# SCH_ESP32-S3-DevKitC-1_2026-10-10.net
KiCad netlist of a schematic drawn in EasyEDA
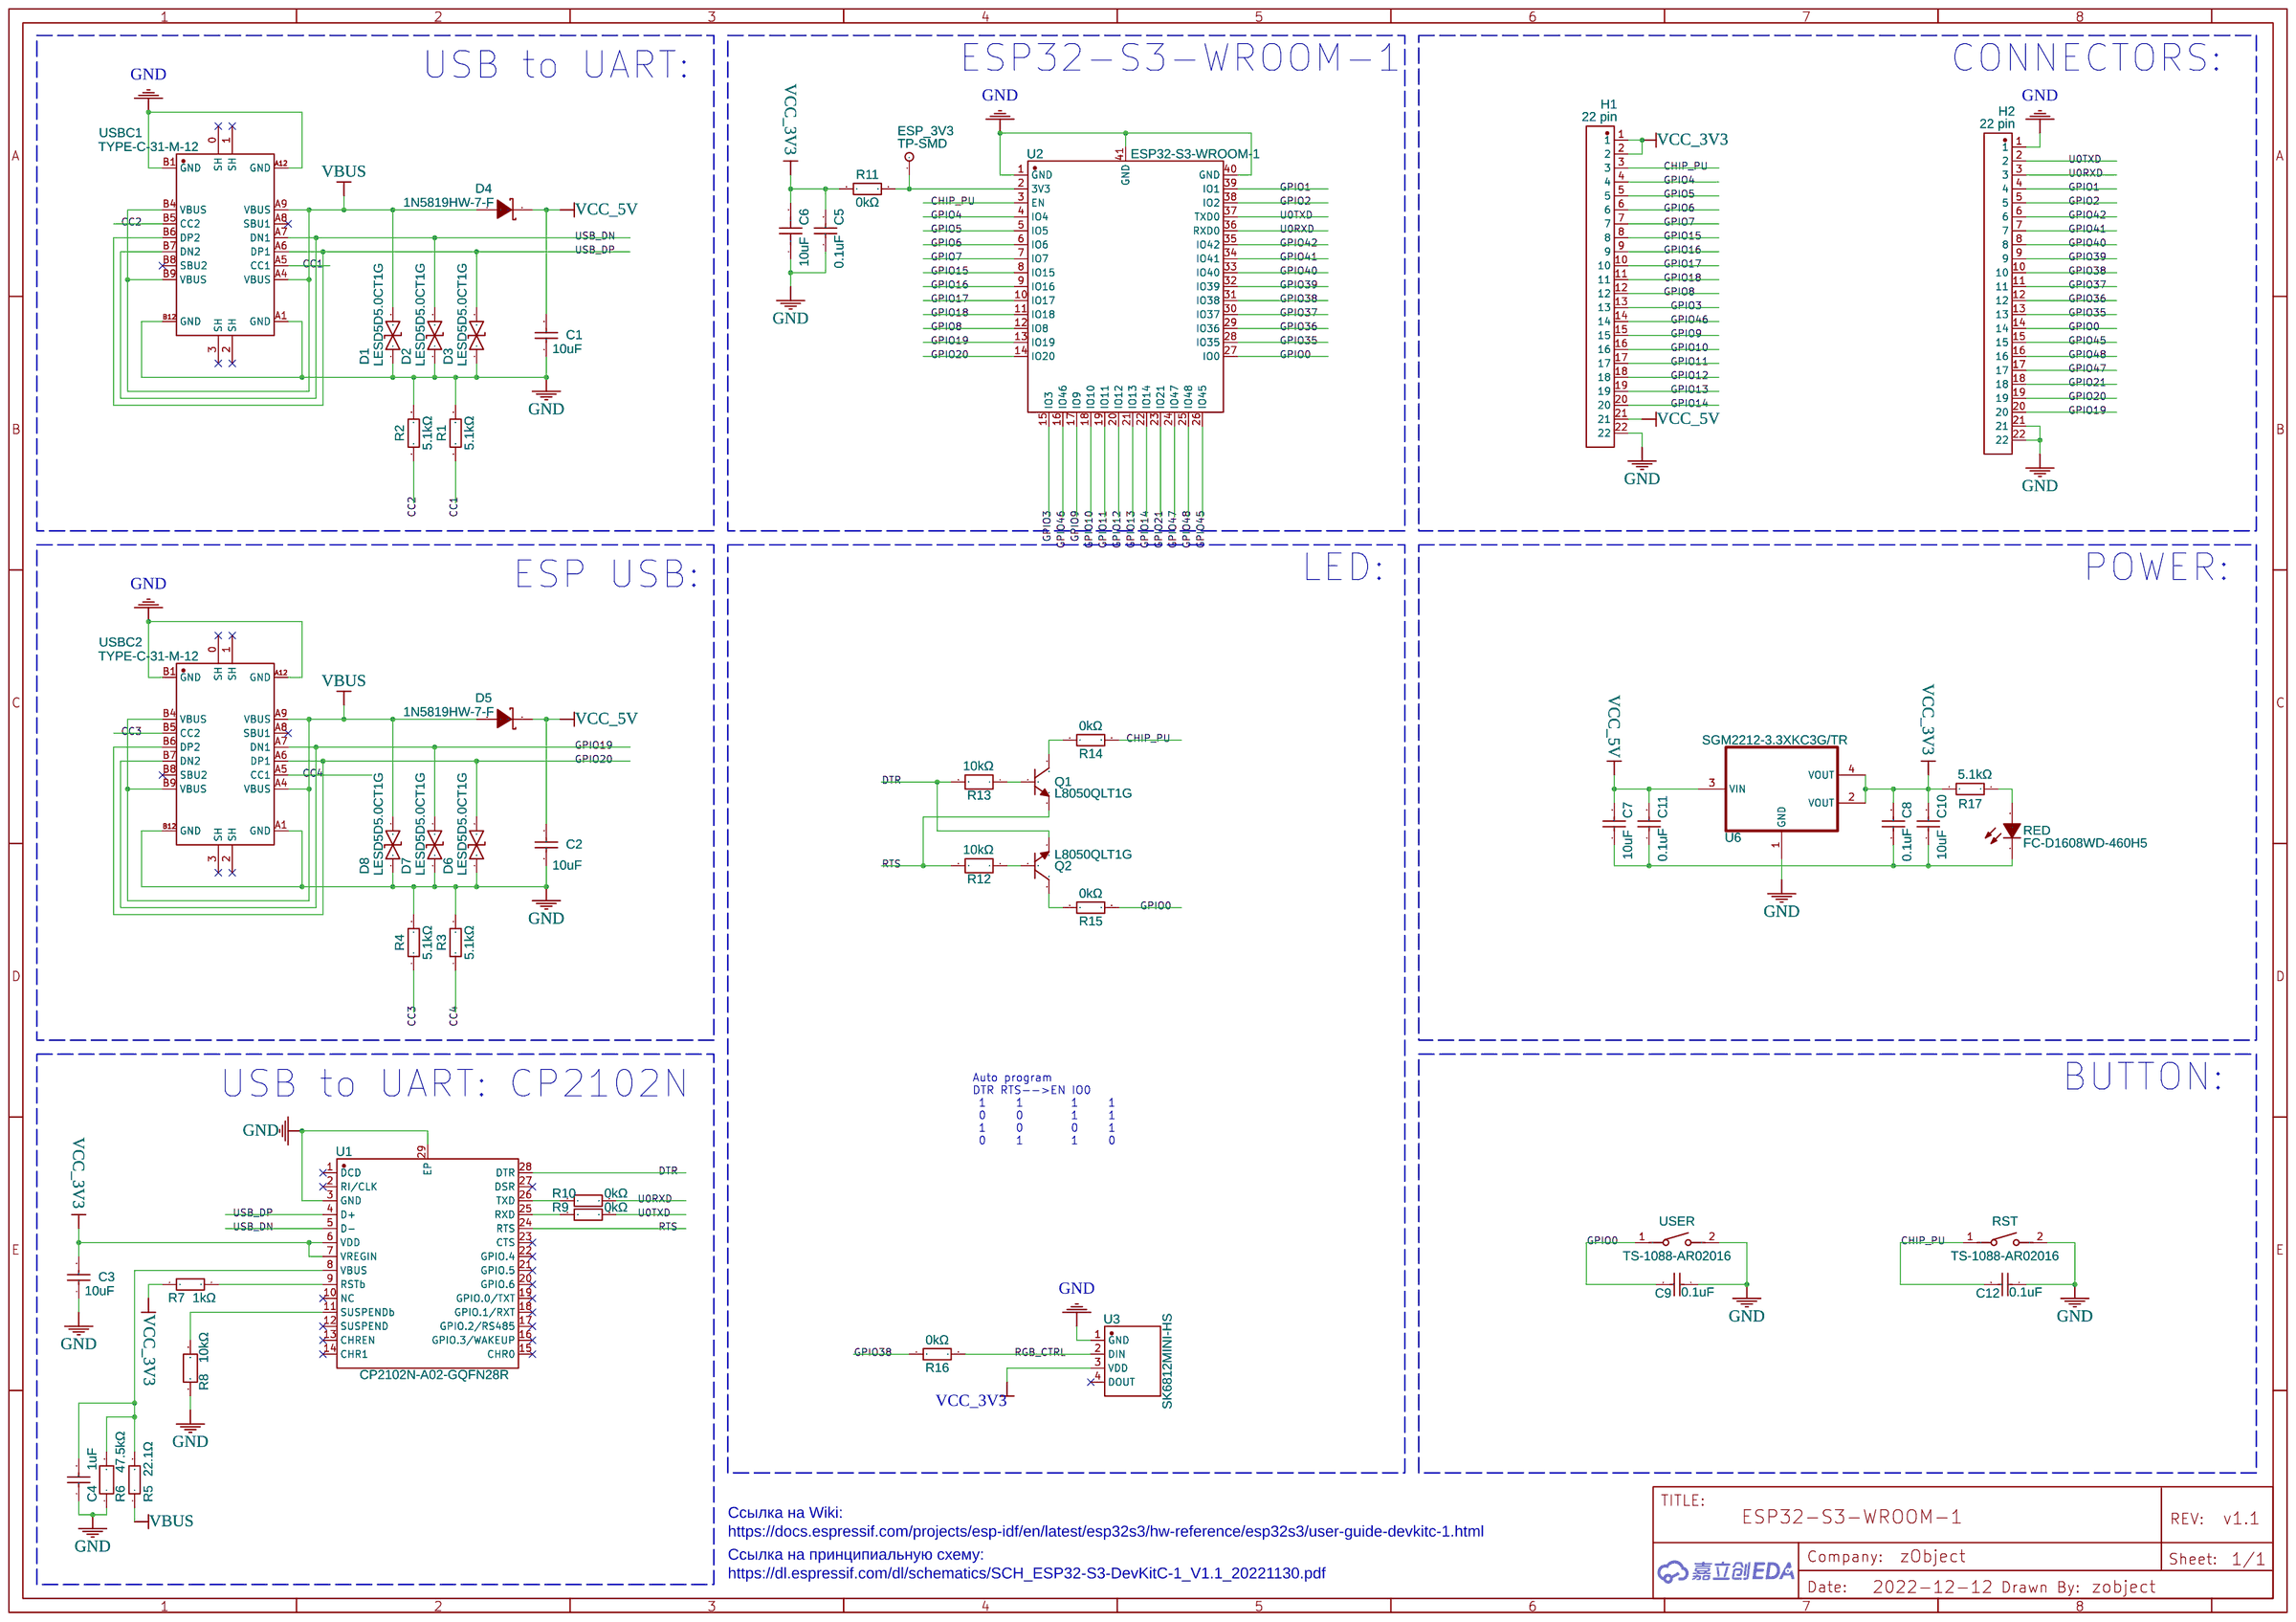
[diagram p0: schematic sheet]

(export (version "E")
  (design (tool "Eeschema 10.0.6"))
  (components
    (comp (ref "C1")
      (value "10uF")
      (fields (field (name "Manufacturer Part") "0603F106M160NT") (field (name "Manufacturer") "FH"))
      (libsource (lib "") (part "0603F106M160NT"))
    )
    (comp (ref "C2")
      (value "10uF")
      (fields (field (name "Manufacturer Part") "0603F106M160NT") (field (name "Manufacturer") "FH"))
      (libsource (lib "") (part "0603F106M160NT"))
    )
    (comp (ref "C3")
      (value "10uF")
      (fields (field (name "Manufacturer Part") "0603F106M160NT") (field (name "Manufacturer") "FH"))
      (libsource (lib "") (part "0603F106M160NT"))
    )
    (comp (ref "C4")
      (value "1uF")
      (fields (field (name "Manufacturer Part") "C1608X5R1C105KT000N") (field (name "Manufacturer") "TDK"))
      (libsource (lib "") (part "C1608X5R1C105KT000N"))
    )
    (comp (ref "C5")
      (value "0.1uF")
      (fields (field (name "Manufacturer Part") "0603B104K500NT") (field (name "Manufacturer") "FH(风华)"))
      (libsource (lib "") (part "0603B104K500NT_1"))
    )
    (comp (ref "C6")
      (value "10uF")
      (fields
        (field (name "Manufacturer Part") "LMK107BJ106MALTD")
        (field (name "Manufacturer") "TAIYO YUDEN")
      )
      (libsource (lib "") (part "LMK107BJ106MALTD"))
    )
    (comp (ref "C7")
      (value "10uF")
      (fields (field (name "Manufacturer Part") "0603F106M160NT") (field (name "Manufacturer") "FH"))
      (libsource (lib "") (part "0603F106M160NT"))
    )
    (comp (ref "C8")
      (value "0.1uF")
      (fields (field (name "Manufacturer Part") "0603B104K500NT") (field (name "Manufacturer") "FH(风华)"))
      (libsource (lib "") (part "0603B104K500NT_1"))
    )
    (comp (ref "C9")
      (value "0.1uF")
      (fields (field (name "Manufacturer Part") "0603B104K500NT") (field (name "Manufacturer") "FH(风华)"))
      (libsource (lib "") (part "0603B104K500NT"))
    )
    (comp (ref "C10")
      (value "10uF")
      (fields (field (name "Manufacturer Part") "0603F106M160NT") (field (name "Manufacturer") "FH"))
      (libsource (lib "") (part "0603F106M160NT"))
    )
    (comp (ref "C11")
      (value "0.1uF")
      (fields (field (name "Manufacturer Part") "0603B104K500NT") (field (name "Manufacturer") "FH(风华)"))
      (libsource (lib "") (part "0603B104K500NT_1"))
    )
    (comp (ref "C12")
      (value "0.1uF")
      (fields (field (name "Manufacturer Part") "0603B104K500NT") (field (name "Manufacturer") "FH(风华)"))
      (libsource (lib "") (part "0603B104K500NT"))
    )
    (comp (ref "D1")
      (value "LESD5D5.0CT1G")
      (fields (field (name "Manufacturer") "Leshan Radio"))
      (libsource (lib "") (part "LESD5D5.0CT1G"))
    )
    (comp (ref "D2")
      (value "LESD5D5.0CT1G")
      (fields (field (name "Manufacturer") "Leshan Radio"))
      (libsource (lib "") (part "LESD5D5.0CT1G"))
    )
    (comp (ref "D3")
      (value "LESD5D5.0CT1G")
      (fields (field (name "Manufacturer") "Leshan Radio"))
      (libsource (lib "") (part "LESD5D5.0CT1G"))
    )
    (comp (ref "D4")
      (value "1N5819HW-7-F")
      (fields (field (name "Manufacturer") "DIODES(美台)"))
      (libsource (lib "") (part "1N5819HW-7-F"))
    )
    (comp (ref "D5")
      (value "1N5819HW-7-F")
      (fields (field (name "Manufacturer") "DIODES(美台)"))
      (libsource (lib "") (part "1N5819HW-7-F"))
    )
    (comp (ref "D6")
      (value "LESD5D5.0CT1G")
      (fields (field (name "Manufacturer") "Leshan Radio"))
      (libsource (lib "") (part "LESD5D5.0CT1G"))
    )
    (comp (ref "D7")
      (value "LESD5D5.0CT1G")
      (fields (field (name "Manufacturer") "Leshan Radio"))
      (libsource (lib "") (part "LESD5D5.0CT1G"))
    )
    (comp (ref "D8")
      (value "LESD5D5.0CT1G")
      (fields (field (name "Manufacturer") "Leshan Radio"))
      (libsource (lib "") (part "LESD5D5.0CT1G"))
    )
    (comp (ref "ESP_3V3") (value "TP-SMD") (libsource (lib "") (part "TP-SMD")))
    (comp (ref "H1")
      (value "22 pin")
      (fields (field (name "Manufacturer Part") "22850120ANG1SYA01") (field (name "Manufacturer") "JILN(锦凌)"))
      (libsource (lib "") (part "22 pin"))
    )
    (comp (ref "H2")
      (value "22 pin")
      (fields (field (name "Manufacturer Part") "22850120ANG1SYA01") (field (name "Manufacturer") "JILN(锦凌)"))
      (libsource (lib "") (part "22 pin"))
    )
    (comp (ref "Q1")
      (value "L8050QLT1G")
      (fields (field (name "Manufacturer") "LRC(乐山无线电)"))
      (libsource (lib "") (part "L8050QLT1G_1"))
    )
    (comp (ref "Q2")
      (value "L8050QLT1G")
      (fields (field (name "Manufacturer") "LRC(乐山无线电)"))
      (libsource (lib "") (part "L8050QLT1G"))
    )
    (comp (ref "R1")
      (value "5.1kΩ")
      (fields (field (name "Manufacturer Part") "RTT035101BTP") (field (name "Manufacturer") "RALEC(旺诠)"))
      (libsource (lib "") (part "RTT035101BTP"))
    )
    (comp (ref "R2")
      (value "5.1kΩ")
      (fields (field (name "Manufacturer Part") "RTT035101BTP") (field (name "Manufacturer") "RALEC(旺诠)"))
      (libsource (lib "") (part "RTT035101BTP"))
    )
    (comp (ref "R3")
      (value "5.1kΩ")
      (fields (field (name "Manufacturer Part") "RTT035101BTP") (field (name "Manufacturer") "RALEC(旺诠)"))
      (libsource (lib "") (part "RTT035101BTP"))
    )
    (comp (ref "R4")
      (value "5.1kΩ")
      (fields (field (name "Manufacturer Part") "RTT035101BTP") (field (name "Manufacturer") "RALEC(旺诠)"))
      (libsource (lib "") (part "RTT035101BTP"))
    )
    (comp (ref "R5")
      (value "22.1Ω")
      (fields (field (name "Manufacturer Part") "RCT0322R1FLF") (field (name "Manufacturer") "HKR"))
      (libsource (lib "") (part "RCT0322R1FLF"))
    )
    (comp (ref "R6")
      (value "47.5kΩ")
      (fields (field (name "Manufacturer Part") "ERJPB3B4752V") (field (name "Manufacturer") "PANASONIC(松下)"))
      (libsource (lib "") (part "ERJPB3B4752V"))
    )
    (comp (ref "R7")
      (value "1kΩ")
      (fields (field (name "Manufacturer Part") "RN73H1JTTD1001B25") (field (name "Manufacturer") "KOA"))
      (libsource (lib "") (part "RN73H1JTTD1001B25"))
    )
    (comp (ref "R8")
      (value "10kΩ")
      (fields (field (name "Manufacturer Part") "CR-03JA7---10K") (field (name "Manufacturer") "Viking(光颉)"))
      (libsource (lib "") (part "CR-03JA7---10K_1"))
    )
    (comp (ref "R9")
      (value "0kΩ")
      (fields (field (name "Manufacturer Part") "RN73H1JTTD1001B25") (field (name "Manufacturer") "KOA"))
      (libsource (lib "") (part "RN73H1JTTD1001B25"))
    )
    (comp (ref "R10")
      (value "0kΩ")
      (fields (field (name "Manufacturer Part") "RN73H1JTTD1001B25") (field (name "Manufacturer") "KOA"))
      (libsource (lib "") (part "RN73H1JTTD1001B25"))
    )
    (comp (ref "R11")
      (value "0kΩ")
      (fields (field (name "Manufacturer Part") "RN73H1JTTD1001B25") (field (name "Manufacturer") "KOA"))
      (libsource (lib "") (part "RN73H1JTTD1001B25"))
    )
    (comp (ref "R12")
      (value "10kΩ")
      (fields (field (name "Manufacturer Part") "CR-03JA7---10K") (field (name "Manufacturer") "Viking(光颉)"))
      (libsource (lib "") (part "CR-03JA7---10K"))
    )
    (comp (ref "R13")
      (value "10kΩ")
      (fields (field (name "Manufacturer Part") "CR-03JA7---10K") (field (name "Manufacturer") "Viking(光颉)"))
      (libsource (lib "") (part "CR-03JA7---10K"))
    )
    (comp (ref "R14")
      (value "0kΩ")
      (fields (field (name "Manufacturer Part") "RN73H1JTTD1001B25") (field (name "Manufacturer") "KOA"))
      (libsource (lib "") (part "RN73H1JTTD1001B25"))
    )
    (comp (ref "R15")
      (value "0kΩ")
      (fields (field (name "Manufacturer Part") "RN73H1JTTD1001B25") (field (name "Manufacturer") "KOA"))
      (libsource (lib "") (part "RN73H1JTTD1001B25"))
    )
    (comp (ref "R16")
      (value "0kΩ")
      (fields (field (name "Manufacturer Part") "RN73H1JTTD1001B25") (field (name "Manufacturer") "KOA"))
      (libsource (lib "") (part "RN73H1JTTD1001B25"))
    )
    (comp (ref "R17")
      (value "5.1kΩ")
      (fields (field (name "Manufacturer Part") "RTT035101BTP") (field (name "Manufacturer") "RALEC(旺诠)"))
      (libsource (lib "") (part "RTT035101BTP_1"))
    )
    (comp (ref "RED")
      (value "FC-D1608WD-460H5")
      (fields (field (name "Manufacturer Part") "NCD0603W1") (field (name "Manufacturer") "国星光电"))
      (libsource (lib "") (part "FC-D1608WD-460H5"))
    )
    (comp (ref "RST")
      (value "TS-1088-AR02016")
      (fields (field (name "Manufacturer") "XUNPU(讯普)"))
      (libsource (lib "") (part "TS-1088-AR02016"))
    )
    (comp (ref "U1")
      (value "CP2102N-A02-GQFN28R")
      (fields (field (name "Manufacturer") "SILICON LABS(芯科)"))
      (libsource (lib "") (part "CP2102N-A02-GQFN28R"))
    )
    (comp (ref "U2")
      (value "ESP32-S3-WROOM-1")
      (fields
        (field (name "Manufacturer Part") "ESP32-S3-WROOM-1(N8R8)")
        (field (name "Manufacturer") "ESPRESSIF(乐鑫)")
      )
      (libsource (lib "") (part "ESP32-S3-WROOM-1(N8R8)"))
    )
    (comp (ref "U3") (value "SK6812MINI-HS") (libsource (lib "") (part "SK6812MINI-HS")))
    (comp (ref "U6") (value "SGM2212-3.3XKC3G/TR") (libsource (lib "") (part "SGM2212-3.3XKC3G/TR")))
    (comp (ref "USBC1")
      (value "TYPE-C-31-M-12")
      (fields (field (name "Manufacturer") "韩国韩荣"))
      (libsource (lib "") (part "TYPE-C-31-M-12"))
    )
    (comp (ref "USBC2")
      (value "TYPE-C-31-M-12")
      (fields (field (name "Manufacturer") "韩国韩荣"))
      (libsource (lib "") (part "TYPE-C-31-M-12"))
    )
    (comp (ref "USER")
      (value "TS-1088-AR02016")
      (fields (field (name "Manufacturer") "XUNPU(讯普)"))
      (libsource (lib "") (part "TS-1088-AR02016_1"))
    )
  )
  (nets
    (net (code "1") (name "/CC1") (class "Default")
      (node (ref "R1") (pin "1") (pinfunction "1_1") (pintype "unspecified"))
      (node (ref "USBC1") (pin "A5") (pinfunction "CC1_A5") (pintype "unspecified"))
    )
    (net (code "2") (name "/CC2") (class "Default")
      (node (ref "R2") (pin "1") (pinfunction "1_1") (pintype "unspecified"))
      (node (ref "USBC1") (pin "B5") (pinfunction "CC2_B5") (pintype "unspecified"))
    )
    (net (code "3") (name "/CC3") (class "Default")
      (node (ref "R4") (pin "1") (pinfunction "1_1") (pintype "unspecified"))
      (node (ref "USBC2") (pin "B5") (pinfunction "CC2_B5") (pintype "unspecified"))
    )
    (net (code "4") (name "/CC4") (class "Default")
      (node (ref "R3") (pin "1") (pinfunction "1_1") (pintype "unspecified"))
      (node (ref "USBC2") (pin "A5") (pinfunction "CC1_A5") (pintype "unspecified"))
    )
    (net (code "5") (name "/CHIP_PU") (class "Default")
      (node (ref "C12") (pin "2") (pinfunction "2_2") (pintype "input"))
      (node (ref "H1") (pin "3") (pinfunction "3_3") (pintype "unspecified"))
      (node (ref "R14") (pin "2") (pinfunction "2_2") (pintype "unspecified"))
      (node (ref "RST") (pin "1") (pinfunction "1_1") (pintype "unspecified"))
      (node (ref "U2") (pin "3") (pinfunction "EN_3") (pintype "unspecified"))
    )
    (net (code "6") (name "/DTR") (class "Default")
      (node (ref "Q2") (pin "2") (pinfunction "E_2") (pintype "unspecified"))
      (node (ref "R13") (pin "2") (pinfunction "2_2") (pintype "unspecified"))
      (node (ref "U1") (pin "28") (pinfunction "DTR_28") (pintype "unspecified"))
    )
    (net (code "7") (name "/GPIO0") (class "Default")
      (node (ref "C9") (pin "2") (pinfunction "2_2") (pintype "input"))
      (node (ref "H2") (pin "14") (pinfunction "14_14") (pintype "unspecified"))
      (node (ref "R15") (pin "2") (pinfunction "2_2") (pintype "unspecified"))
      (node (ref "U2") (pin "27") (pinfunction "IO0_27") (pintype "unspecified"))
      (node (ref "USER") (pin "1") (pinfunction "1_1") (pintype "unspecified"))
    )
    (net (code "8") (name "/GPIO1") (class "Default")
      (node (ref "H2") (pin "4") (pinfunction "4_4") (pintype "unspecified"))
      (node (ref "U2") (pin "39") (pinfunction "IO1_39") (pintype "unspecified"))
    )
    (net (code "9") (name "/GPIO2") (class "Default")
      (node (ref "H2") (pin "5") (pinfunction "5_5") (pintype "unspecified"))
      (node (ref "U2") (pin "38") (pinfunction "IO2_38") (pintype "unspecified"))
    )
    (net (code "10") (name "/GPIO3") (class "Default")
      (node (ref "H1") (pin "13") (pinfunction "13_13") (pintype "unspecified"))
      (node (ref "U2") (pin "15") (pinfunction "IO3_15") (pintype "unspecified"))
    )
    (net (code "11") (name "/GPIO4") (class "Default")
      (node (ref "H1") (pin "4") (pinfunction "4_4") (pintype "unspecified"))
      (node (ref "U2") (pin "4") (pinfunction "IO4_4") (pintype "unspecified"))
    )
    (net (code "12") (name "/GPIO5") (class "Default")
      (node (ref "H1") (pin "5") (pinfunction "5_5") (pintype "unspecified"))
      (node (ref "U2") (pin "5") (pinfunction "IO5_5") (pintype "unspecified"))
    )
    (net (code "13") (name "/GPIO6") (class "Default")
      (node (ref "H1") (pin "6") (pinfunction "6_6") (pintype "unspecified"))
      (node (ref "U2") (pin "6") (pinfunction "IO6_6") (pintype "unspecified"))
    )
    (net (code "14") (name "/GPIO7") (class "Default")
      (node (ref "H1") (pin "7") (pinfunction "7_7") (pintype "unspecified"))
      (node (ref "U2") (pin "7") (pinfunction "IO7_7") (pintype "unspecified"))
    )
    (net (code "15") (name "/GPIO8") (class "Default")
      (node (ref "H1") (pin "12") (pinfunction "12_12") (pintype "unspecified"))
      (node (ref "U2") (pin "12") (pinfunction "IO8_12") (pintype "unspecified"))
    )
    (net (code "16") (name "/GPIO9") (class "Default")
      (node (ref "H1") (pin "15") (pinfunction "15_15") (pintype "unspecified"))
      (node (ref "U2") (pin "17") (pinfunction "IO9_17") (pintype "unspecified"))
    )
    (net (code "17") (name "/GPIO10") (class "Default")
      (node (ref "H1") (pin "16") (pinfunction "16_16") (pintype "unspecified"))
      (node (ref "U2") (pin "18") (pinfunction "IO10_18") (pintype "unspecified"))
    )
    (net (code "18") (name "/GPIO11") (class "Default")
      (node (ref "H1") (pin "17") (pinfunction "17_17") (pintype "unspecified"))
      (node (ref "U2") (pin "19") (pinfunction "IO11_19") (pintype "unspecified"))
    )
    (net (code "19") (name "/GPIO12") (class "Default")
      (node (ref "H1") (pin "18") (pinfunction "18_18") (pintype "unspecified"))
      (node (ref "U2") (pin "20") (pinfunction "IO12_20") (pintype "unspecified"))
    )
    (net (code "20") (name "/GPIO13") (class "Default")
      (node (ref "H1") (pin "19") (pinfunction "19_19") (pintype "unspecified"))
      (node (ref "U2") (pin "21") (pinfunction "IO13_21") (pintype "unspecified"))
    )
    (net (code "21") (name "/GPIO14") (class "Default")
      (node (ref "H1") (pin "20") (pinfunction "20_20") (pintype "unspecified"))
      (node (ref "U2") (pin "22") (pinfunction "IO14_22") (pintype "unspecified"))
    )
    (net (code "22") (name "/GPIO15") (class "Default")
      (node (ref "H1") (pin "8") (pinfunction "8_8") (pintype "unspecified"))
      (node (ref "U2") (pin "8") (pinfunction "IO15_8") (pintype "unspecified"))
    )
    (net (code "23") (name "/GPIO16") (class "Default")
      (node (ref "H1") (pin "9") (pinfunction "9_9") (pintype "unspecified"))
      (node (ref "U2") (pin "9") (pinfunction "IO16_9") (pintype "unspecified"))
    )
    (net (code "24") (name "/GPIO17") (class "Default")
      (node (ref "H1") (pin "10") (pinfunction "10_10") (pintype "unspecified"))
      (node (ref "U2") (pin "10") (pinfunction "IO17_10") (pintype "unspecified"))
    )
    (net (code "25") (name "/GPIO18") (class "Default")
      (node (ref "H1") (pin "11") (pinfunction "11_11") (pintype "unspecified"))
      (node (ref "U2") (pin "11") (pinfunction "IO18_11") (pintype "unspecified"))
    )
    (net (code "26") (name "/GPIO19") (class "Default")
      (node (ref "D7") (pin "2") (pinfunction "2_2") (pintype "unspecified"))
      (node (ref "H2") (pin "20") (pinfunction "20_20") (pintype "unspecified"))
      (node (ref "U2") (pin "13") (pinfunction "IO19_13") (pintype "unspecified"))
      (node (ref "USBC2") (pin "A7") (pinfunction "DN1_A7") (pintype "unspecified"))
      (node (ref "USBC2") (pin "B7") (pinfunction "DN2_B7") (pintype "unspecified"))
    )
    (net (code "27") (name "/GPIO20") (class "Default")
      (node (ref "D6") (pin "2") (pinfunction "2_2") (pintype "unspecified"))
      (node (ref "H2") (pin "19") (pinfunction "19_19") (pintype "unspecified"))
      (node (ref "U2") (pin "14") (pinfunction "IO20_14") (pintype "unspecified"))
      (node (ref "USBC2") (pin "A6") (pinfunction "DP1_A6") (pintype "unspecified"))
      (node (ref "USBC2") (pin "B6") (pinfunction "DP2_B6") (pintype "unspecified"))
    )
    (net (code "28") (name "/GPIO21") (class "Default")
      (node (ref "H2") (pin "18") (pinfunction "18_18") (pintype "unspecified"))
      (node (ref "U2") (pin "23") (pinfunction "IO21_23") (pintype "unspecified"))
    )
    (net (code "29") (name "/GPIO35") (class "Default")
      (node (ref "H2") (pin "13") (pinfunction "13_13") (pintype "unspecified"))
      (node (ref "U2") (pin "28") (pinfunction "IO35_28") (pintype "unspecified"))
    )
    (net (code "30") (name "/GPIO36") (class "Default")
      (node (ref "H2") (pin "12") (pinfunction "12_12") (pintype "unspecified"))
      (node (ref "U2") (pin "29") (pinfunction "IO36_29") (pintype "unspecified"))
    )
    (net (code "31") (name "/GPIO37") (class "Default")
      (node (ref "H2") (pin "11") (pinfunction "11_11") (pintype "unspecified"))
      (node (ref "U2") (pin "30") (pinfunction "IO37_30") (pintype "unspecified"))
    )
    (net (code "32") (name "/GPIO38") (class "Default")
      (node (ref "H2") (pin "10") (pinfunction "10_10") (pintype "unspecified"))
      (node (ref "R16") (pin "1") (pinfunction "1_1") (pintype "unspecified"))
      (node (ref "U2") (pin "31") (pinfunction "IO38_31") (pintype "unspecified"))
    )
    (net (code "33") (name "/GPIO39") (class "Default")
      (node (ref "H2") (pin "9") (pinfunction "9_9") (pintype "unspecified"))
      (node (ref "U2") (pin "32") (pinfunction "IO39_32") (pintype "unspecified"))
    )
    (net (code "34") (name "/GPIO40") (class "Default")
      (node (ref "H2") (pin "8") (pinfunction "8_8") (pintype "unspecified"))
      (node (ref "U2") (pin "33") (pinfunction "IO40_33") (pintype "unspecified"))
    )
    (net (code "35") (name "/GPIO41") (class "Default")
      (node (ref "H2") (pin "7") (pinfunction "7_7") (pintype "unspecified"))
      (node (ref "U2") (pin "34") (pinfunction "IO41_34") (pintype "unspecified"))
    )
    (net (code "36") (name "/GPIO42") (class "Default")
      (node (ref "H2") (pin "6") (pinfunction "6_6") (pintype "unspecified"))
      (node (ref "U2") (pin "35") (pinfunction "IO42_35") (pintype "unspecified"))
    )
    (net (code "37") (name "/GPIO45") (class "Default")
      (node (ref "H2") (pin "15") (pinfunction "15_15") (pintype "unspecified"))
      (node (ref "U2") (pin "26") (pinfunction "IO45_26") (pintype "unspecified"))
    )
    (net (code "38") (name "/GPIO46") (class "Default")
      (node (ref "H1") (pin "14") (pinfunction "14_14") (pintype "unspecified"))
      (node (ref "U2") (pin "16") (pinfunction "IO46_16") (pintype "unspecified"))
    )
    (net (code "39") (name "/GPIO47") (class "Default")
      (node (ref "H2") (pin "17") (pinfunction "17_17") (pintype "unspecified"))
      (node (ref "U2") (pin "24") (pinfunction "IO47_24") (pintype "unspecified"))
    )
    (net (code "40") (name "/GPIO48") (class "Default")
      (node (ref "H2") (pin "16") (pinfunction "16_16") (pintype "unspecified"))
      (node (ref "U2") (pin "25") (pinfunction "IO48_25") (pintype "unspecified"))
    )
    (net (code "41") (name "/RGB_CTRL") (class "Default")
      (node (ref "R16") (pin "2") (pinfunction "2_2") (pintype "unspecified"))
      (node (ref "U3") (pin "2") (pinfunction "DIN_2") (pintype "unspecified"))
    )
    (net (code "42") (name "/RTS") (class "Default")
      (node (ref "Q1") (pin "2") (pinfunction "E_2") (pintype "unspecified"))
      (node (ref "R12") (pin "2") (pinfunction "2_2") (pintype "unspecified"))
      (node (ref "U1") (pin "24") (pinfunction "RTS_24") (pintype "unspecified"))
    )
    (net (code "43") (name "/U0RXD") (class "Default")
      (node (ref "H2") (pin "3") (pinfunction "3_3") (pintype "unspecified"))
      (node (ref "R10") (pin "2") (pinfunction "2_2") (pintype "unspecified"))
      (node (ref "U2") (pin "36") (pinfunction "RXD0_36") (pintype "unspecified"))
    )
    (net (code "44") (name "/U0TXD") (class "Default")
      (node (ref "H2") (pin "2") (pinfunction "2_2") (pintype "unspecified"))
      (node (ref "R9") (pin "2") (pinfunction "2_2") (pintype "unspecified"))
      (node (ref "U2") (pin "37") (pinfunction "TXD0_37") (pintype "unspecified"))
    )
    (net (code "45") (name "/USB_DN") (class "Default")
      (node (ref "D2") (pin "2") (pinfunction "2_2") (pintype "unspecified"))
      (node (ref "U1") (pin "5") (pinfunction "D-_5") (pintype "unspecified"))
      (node (ref "USBC1") (pin "A7") (pinfunction "DN1_A7") (pintype "unspecified"))
      (node (ref "USBC1") (pin "B7") (pinfunction "DN2_B7") (pintype "unspecified"))
    )
    (net (code "46") (name "/USB_DP") (class "Default")
      (node (ref "D3") (pin "2") (pinfunction "2_2") (pintype "unspecified"))
      (node (ref "U1") (pin "4") (pinfunction "D+_4") (pintype "unspecified"))
      (node (ref "USBC1") (pin "A6") (pinfunction "DP1_A6") (pintype "unspecified"))
      (node (ref "USBC1") (pin "B6") (pinfunction "DP2_B6") (pintype "unspecified"))
    )
    (net (code "47") (name "GND") (class "Default")
      (node (ref "C1") (pin "1") (pinfunction "1_1") (pintype "input"))
      (node (ref "C10") (pin "1") (pinfunction "1_1") (pintype "input"))
      (node (ref "C11") (pin "1") (pinfunction "1_1") (pintype "input"))
      (node (ref "C12") (pin "1") (pinfunction "1_1") (pintype "input"))
      (node (ref "C2") (pin "1") (pinfunction "1_1") (pintype "input"))
      (node (ref "C3") (pin "1") (pinfunction "1_1") (pintype "input"))
      (node (ref "C4") (pin "1") (pinfunction "1_1") (pintype "input"))
      (node (ref "C5") (pin "1") (pinfunction "1_1") (pintype "input"))
      (node (ref "C6") (pin "1") (pinfunction "1_1") (pintype "unspecified"))
      (node (ref "C7") (pin "1") (pinfunction "1_1") (pintype "input"))
      (node (ref "C8") (pin "1") (pinfunction "1_1") (pintype "input"))
      (node (ref "C9") (pin "1") (pinfunction "1_1") (pintype "input"))
      (node (ref "D1") (pin "1") (pinfunction "1_1") (pintype "unspecified"))
      (node (ref "D2") (pin "1") (pinfunction "1_1") (pintype "unspecified"))
      (node (ref "D3") (pin "1") (pinfunction "1_1") (pintype "unspecified"))
      (node (ref "D6") (pin "1") (pinfunction "1_1") (pintype "unspecified"))
      (node (ref "D7") (pin "1") (pinfunction "1_1") (pintype "unspecified"))
      (node (ref "D8") (pin "1") (pinfunction "1_1") (pintype "unspecified"))
      (node (ref "H1") (pin "22") (pinfunction "22_22") (pintype "unspecified"))
      (node (ref "H2") (pin "1") (pinfunction "1_1") (pintype "unspecified"))
      (node (ref "H2") (pin "21") (pinfunction "21_21") (pintype "unspecified"))
      (node (ref "H2") (pin "22") (pinfunction "22_22") (pintype "unspecified"))
      (node (ref "R1") (pin "2") (pinfunction "2_2") (pintype "unspecified"))
      (node (ref "R2") (pin "2") (pinfunction "2_2") (pintype "unspecified"))
      (node (ref "R3") (pin "2") (pinfunction "2_2") (pintype "unspecified"))
      (node (ref "R4") (pin "2") (pinfunction "2_2") (pintype "unspecified"))
      (node (ref "R6") (pin "1") (pinfunction "1_1") (pintype "unspecified"))
      (node (ref "R8") (pin "1") (pinfunction "1_1") (pintype "unspecified"))
      (node (ref "RED") (pin "1") (pinfunction "-_1") (pintype "input"))
      (node (ref "RST") (pin "2") (pinfunction "2_2") (pintype "unspecified"))
      (node (ref "U1") (pin "29") (pinfunction "EP_29") (pintype "unspecified"))
      (node (ref "U1") (pin "3") (pinfunction "GND_3") (pintype "unspecified"))
      (node (ref "U2") (pin "1") (pinfunction "GND_1") (pintype "unspecified"))
      (node (ref "U2") (pin "40") (pinfunction "GND_40") (pintype "unspecified"))
      (node (ref "U2") (pin "41") (pinfunction "GND_41") (pintype "unspecified"))
      (node (ref "U3") (pin "1") (pinfunction "GND_1") (pintype "unspecified"))
      (node (ref "U6") (pin "1") (pinfunction "GND_1") (pintype "unspecified"))
      (node (ref "USBC1") (pin "A1") (pinfunction "GND_A1") (pintype "unspecified"))
      (node (ref "USBC1") (pin "A12") (pinfunction "GND_A12") (pintype "unspecified"))
      (node (ref "USBC1") (pin "B1") (pinfunction "GND_B1") (pintype "unspecified"))
      (node (ref "USBC1") (pin "B12") (pinfunction "GND_B12") (pintype "unspecified"))
      (node (ref "USBC2") (pin "A1") (pinfunction "GND_A1") (pintype "unspecified"))
      (node (ref "USBC2") (pin "A12") (pinfunction "GND_A12") (pintype "unspecified"))
      (node (ref "USBC2") (pin "B1") (pinfunction "GND_B1") (pintype "unspecified"))
      (node (ref "USBC2") (pin "B12") (pinfunction "GND_B12") (pintype "unspecified"))
      (node (ref "USER") (pin "2") (pinfunction "2_2") (pintype "unspecified"))
    )
    (net (code "48") (name "Net-(Q1-B)") (class "Default")
      (node (ref "Q1") (pin "1") (pinfunction "B_1") (pintype "unspecified"))
      (node (ref "R13") (pin "1") (pinfunction "1_1") (pintype "unspecified"))
    )
    (net (code "49") (name "Net-(Q1-C)") (class "Default")
      (node (ref "Q1") (pin "3") (pinfunction "C_3") (pintype "unspecified"))
      (node (ref "R14") (pin "1") (pinfunction "1_1") (pintype "unspecified"))
    )
    (net (code "50") (name "Net-(Q2-B)") (class "Default")
      (node (ref "Q2") (pin "1") (pinfunction "B_1") (pintype "unspecified"))
      (node (ref "R12") (pin "1") (pinfunction "1_1") (pintype "unspecified"))
    )
    (net (code "51") (name "Net-(Q2-C)") (class "Default")
      (node (ref "Q2") (pin "3") (pinfunction "C_3") (pintype "unspecified"))
      (node (ref "R15") (pin "1") (pinfunction "1_1") (pintype "unspecified"))
    )
    (net (code "52") (name "Net-(RED-+)") (class "Default")
      (node (ref "R17") (pin "1") (pinfunction "1_1") (pintype "unspecified"))
      (node (ref "RED") (pin "2") (pinfunction "+_2") (pintype "input"))
    )
    (net (code "53") (name "Net-(U1-RSTb)") (class "Default")
      (node (ref "R7") (pin "2") (pinfunction "2_2") (pintype "unspecified"))
      (node (ref "U1") (pin "9") (pinfunction "RSTb_9") (pintype "unspecified"))
    )
    (net (code "54") (name "Net-(U1-RXD)") (class "Default")
      (node (ref "R9") (pin "1") (pinfunction "1_1") (pintype "unspecified"))
      (node (ref "U1") (pin "25") (pinfunction "RXD_25") (pintype "unspecified"))
    )
    (net (code "55") (name "Net-(U1-SUSPENDb)") (class "Default")
      (node (ref "R8") (pin "2") (pinfunction "2_2") (pintype "unspecified"))
      (node (ref "U1") (pin "11") (pinfunction "SUSPENDb_11") (pintype "unspecified"))
    )
    (net (code "56") (name "Net-(U1-TXD)") (class "Default")
      (node (ref "R10") (pin "1") (pinfunction "1_1") (pintype "unspecified"))
      (node (ref "U1") (pin "26") (pinfunction "TXD_26") (pintype "unspecified"))
    )
    (net (code "57") (name "Net-(U1-VBUS)") (class "Default")
      (node (ref "C4") (pin "2") (pinfunction "2_2") (pintype "input"))
      (node (ref "R5") (pin "2") (pinfunction "2_2") (pintype "unspecified"))
      (node (ref "R6") (pin "2") (pinfunction "2_2") (pintype "unspecified"))
      (node (ref "U1") (pin "8") (pinfunction "VBUS_8") (pintype "unspecified"))
    )
    (net (code "58") (name "Net-(U2-3V3)") (class "Default")
      (node (ref "ESP_3V3") (pin "1") (pinfunction "1_1") (pintype "unspecified"))
      (node (ref "R11") (pin "2") (pinfunction "2_2") (pintype "unspecified"))
      (node (ref "U2") (pin "2") (pinfunction "3V3_2") (pintype "unspecified"))
    )
    (net (code "59") (name "VBUS") (class "Default")
      (node (ref "D1") (pin "2") (pinfunction "2_2") (pintype "unspecified"))
      (node (ref "D4") (pin "1") (pinfunction "A_1") (pintype "unspecified"))
      (node (ref "D5") (pin "1") (pinfunction "A_1") (pintype "unspecified"))
      (node (ref "D8") (pin "2") (pinfunction "2_2") (pintype "unspecified"))
      (node (ref "R5") (pin "1") (pinfunction "1_1") (pintype "unspecified"))
      (node (ref "USBC1") (pin "A4") (pinfunction "VBUS_A4") (pintype "unspecified"))
      (node (ref "USBC1") (pin "A9") (pinfunction "VBUS_A9") (pintype "unspecified"))
      (node (ref "USBC1") (pin "B4") (pinfunction "VBUS_B4") (pintype "unspecified"))
      (node (ref "USBC1") (pin "B9") (pinfunction "VBUS_B9") (pintype "unspecified"))
      (node (ref "USBC2") (pin "A4") (pinfunction "VBUS_A4") (pintype "unspecified"))
      (node (ref "USBC2") (pin "A9") (pinfunction "VBUS_A9") (pintype "unspecified"))
      (node (ref "USBC2") (pin "B4") (pinfunction "VBUS_B4") (pintype "unspecified"))
      (node (ref "USBC2") (pin "B9") (pinfunction "VBUS_B9") (pintype "unspecified"))
    )
    (net (code "60") (name "VCC_3V3") (class "Default")
      (node (ref "C10") (pin "2") (pinfunction "2_2") (pintype "input"))
      (node (ref "C3") (pin "2") (pinfunction "2_2") (pintype "input"))
      (node (ref "C5") (pin "2") (pinfunction "2_2") (pintype "input"))
      (node (ref "C6") (pin "2") (pinfunction "2_2") (pintype "unspecified"))
      (node (ref "C8") (pin "2") (pinfunction "2_2") (pintype "input"))
      (node (ref "H1") (pin "1") (pinfunction "1_1") (pintype "unspecified"))
      (node (ref "H1") (pin "2") (pinfunction "2_2") (pintype "unspecified"))
      (node (ref "R11") (pin "1") (pinfunction "1_1") (pintype "unspecified"))
      (node (ref "R17") (pin "2") (pinfunction "2_2") (pintype "unspecified"))
      (node (ref "R7") (pin "1") (pinfunction "1_1") (pintype "unspecified"))
      (node (ref "U1") (pin "6") (pinfunction "VDD_6") (pintype "unspecified"))
      (node (ref "U1") (pin "7") (pinfunction "VREGIN_7") (pintype "unspecified"))
      (node (ref "U3") (pin "3") (pinfunction "VDD_3") (pintype "unspecified"))
      (node (ref "U6") (pin "2") (pinfunction "VOUT_2") (pintype "unspecified"))
      (node (ref "U6") (pin "4") (pinfunction "VOUT_4") (pintype "unspecified"))
    )
    (net (code "61") (name "VCC_5V") (class "Default")
      (node (ref "C1") (pin "2") (pinfunction "2_2") (pintype "input"))
      (node (ref "C11") (pin "2") (pinfunction "2_2") (pintype "input"))
      (node (ref "C2") (pin "2") (pinfunction "2_2") (pintype "input"))
      (node (ref "C7") (pin "2") (pinfunction "2_2") (pintype "input"))
      (node (ref "D4") (pin "2") (pinfunction "K_2") (pintype "unspecified"))
      (node (ref "D5") (pin "2") (pinfunction "K_2") (pintype "unspecified"))
      (node (ref "H1") (pin "21") (pinfunction "21_21") (pintype "unspecified"))
      (node (ref "U6") (pin "3") (pinfunction "VIN_3") (pintype "unspecified"))
    )
    (net (code "62") (name "unconnected-(U1-CHR0-Pad15)") (class "Default")
      (node (ref "U1") (pin "15") (pinfunction "CHR0_15") (pintype "unspecified+no_connect"))
    )
    (net (code "63") (name "unconnected-(U1-CHR1-Pad14)") (class "Default")
      (node (ref "U1") (pin "14") (pinfunction "CHR1_14") (pintype "unspecified+no_connect"))
    )
    (net (code "64") (name "unconnected-(U1-CHREN-Pad13)") (class "Default")
      (node (ref "U1") (pin "13") (pinfunction "CHREN_13") (pintype "unspecified+no_connect"))
    )
    (net (code "65") (name "unconnected-(U1-CTS-Pad23)") (class "Default")
      (node (ref "U1") (pin "23") (pinfunction "CTS_23") (pintype "unspecified+no_connect"))
    )
    (net (code "66") (name "unconnected-(U1-DCD-Pad1)") (class "Default")
      (node (ref "U1") (pin "1") (pinfunction "DCD_1") (pintype "unspecified+no_connect"))
    )
    (net (code "67") (name "unconnected-(U1-DSR-Pad27)") (class "Default")
      (node (ref "U1") (pin "27") (pinfunction "DSR_27") (pintype "unspecified+no_connect"))
    )
    (net (code "68") (name "unconnected-(U1-GPIO.0{slash}TXT-Pad19)") (class "Default")
      (node (ref "U1") (pin "19") (pinfunction "GPIO.0/TXT_19") (pintype "unspecified+no_connect"))
    )
    (net (code "69") (name "unconnected-(U1-GPIO.1{slash}RXT-Pad18)") (class "Default")
      (node (ref "U1") (pin "18") (pinfunction "GPIO.1/RXT_18") (pintype "unspecified+no_connect"))
    )
    (net (code "70") (name "unconnected-(U1-GPIO.2{slash}RS485-Pad17)") (class "Default")
      (node (ref "U1") (pin "17") (pinfunction "GPIO.2/RS485_17") (pintype "unspecified+no_connect"))
    )
    (net (code "71") (name "unconnected-(U1-GPIO.3{slash}WAKEUP-Pad16)") (class "Default")
      (node (ref "U1") (pin "16") (pinfunction "GPIO.3/WAKEUP_16") (pintype "unspecified+no_connect"))
    )
    (net (code "72") (name "unconnected-(U1-GPIO.4-Pad22)") (class "Default")
      (node (ref "U1") (pin "22") (pinfunction "GPIO.4_22") (pintype "unspecified+no_connect"))
    )
    (net (code "73") (name "unconnected-(U1-GPIO.5-Pad21)") (class "Default")
      (node (ref "U1") (pin "21") (pinfunction "GPIO.5_21") (pintype "unspecified+no_connect"))
    )
    (net (code "74") (name "unconnected-(U1-GPIO.6-Pad20)") (class "Default")
      (node (ref "U1") (pin "20") (pinfunction "GPIO.6_20") (pintype "unspecified+no_connect"))
    )
    (net (code "75") (name "unconnected-(U1-NC-Pad10)") (class "Default")
      (node (ref "U1") (pin "10") (pinfunction "NC_10") (pintype "unspecified+no_connect"))
    )
    (net (code "76") (name "unconnected-(U1-RI{slash}CLK-Pad2)") (class "Default")
      (node (ref "U1") (pin "2") (pinfunction "RI/CLK_2") (pintype "unspecified+no_connect"))
    )
    (net (code "77") (name "unconnected-(U1-SUSPEND-Pad12)") (class "Default")
      (node (ref "U1") (pin "12") (pinfunction "SUSPEND_12") (pintype "unspecified+no_connect"))
    )
    (net (code "78") (name "unconnected-(U3-DOUT-Pad4)") (class "Default")
      (node (ref "U3") (pin "4") (pinfunction "DOUT_4") (pintype "unspecified+no_connect"))
    )
    (net (code "79") (name "unconnected-(USBC1-SBU1-PadA8)") (class "Default")
      (node (ref "USBC1") (pin "A8") (pinfunction "SBU1_A8") (pintype "unspecified+no_connect"))
    )
    (net (code "80") (name "unconnected-(USBC1-SBU2-PadB8)") (class "Default")
      (node (ref "USBC1") (pin "B8") (pinfunction "SBU2_B8") (pintype "unspecified+no_connect"))
    )
    (net (code "81") (name "unconnected-(USBC1-SH-Pad0)") (class "Default")
      (node (ref "USBC1") (pin "0") (pinfunction "SH_0") (pintype "unspecified+no_connect"))
    )
    (net (code "82") (name "unconnected-(USBC1-SH-Pad1)") (class "Default")
      (node (ref "USBC1") (pin "1") (pinfunction "SH_1") (pintype "unspecified+no_connect"))
    )
    (net (code "83") (name "unconnected-(USBC1-SH-Pad2)") (class "Default")
      (node (ref "USBC1") (pin "2") (pinfunction "SH_2") (pintype "unspecified+no_connect"))
    )
    (net (code "84") (name "unconnected-(USBC1-SH-Pad3)") (class "Default")
      (node (ref "USBC1") (pin "3") (pinfunction "SH_3") (pintype "unspecified+no_connect"))
    )
    (net (code "85") (name "unconnected-(USBC2-SBU1-PadA8)") (class "Default")
      (node (ref "USBC2") (pin "A8") (pinfunction "SBU1_A8") (pintype "unspecified+no_connect"))
    )
    (net (code "86") (name "unconnected-(USBC2-SBU2-PadB8)") (class "Default")
      (node (ref "USBC2") (pin "B8") (pinfunction "SBU2_B8") (pintype "unspecified+no_connect"))
    )
    (net (code "87") (name "unconnected-(USBC2-SH-Pad0)") (class "Default")
      (node (ref "USBC2") (pin "0") (pinfunction "SH_0") (pintype "unspecified+no_connect"))
    )
    (net (code "88") (name "unconnected-(USBC2-SH-Pad1)") (class "Default")
      (node (ref "USBC2") (pin "1") (pinfunction "SH_1") (pintype "unspecified+no_connect"))
    )
    (net (code "89") (name "unconnected-(USBC2-SH-Pad2)") (class "Default")
      (node (ref "USBC2") (pin "2") (pinfunction "SH_2") (pintype "unspecified+no_connect"))
    )
    (net (code "90") (name "unconnected-(USBC2-SH-Pad3)") (class "Default")
      (node (ref "USBC2") (pin "3") (pinfunction "SH_3") (pintype "unspecified+no_connect"))
    )
  )
)
